# FTDI-Toolkit.net
KiCad netlist of a schematic drawn in Altium Designer
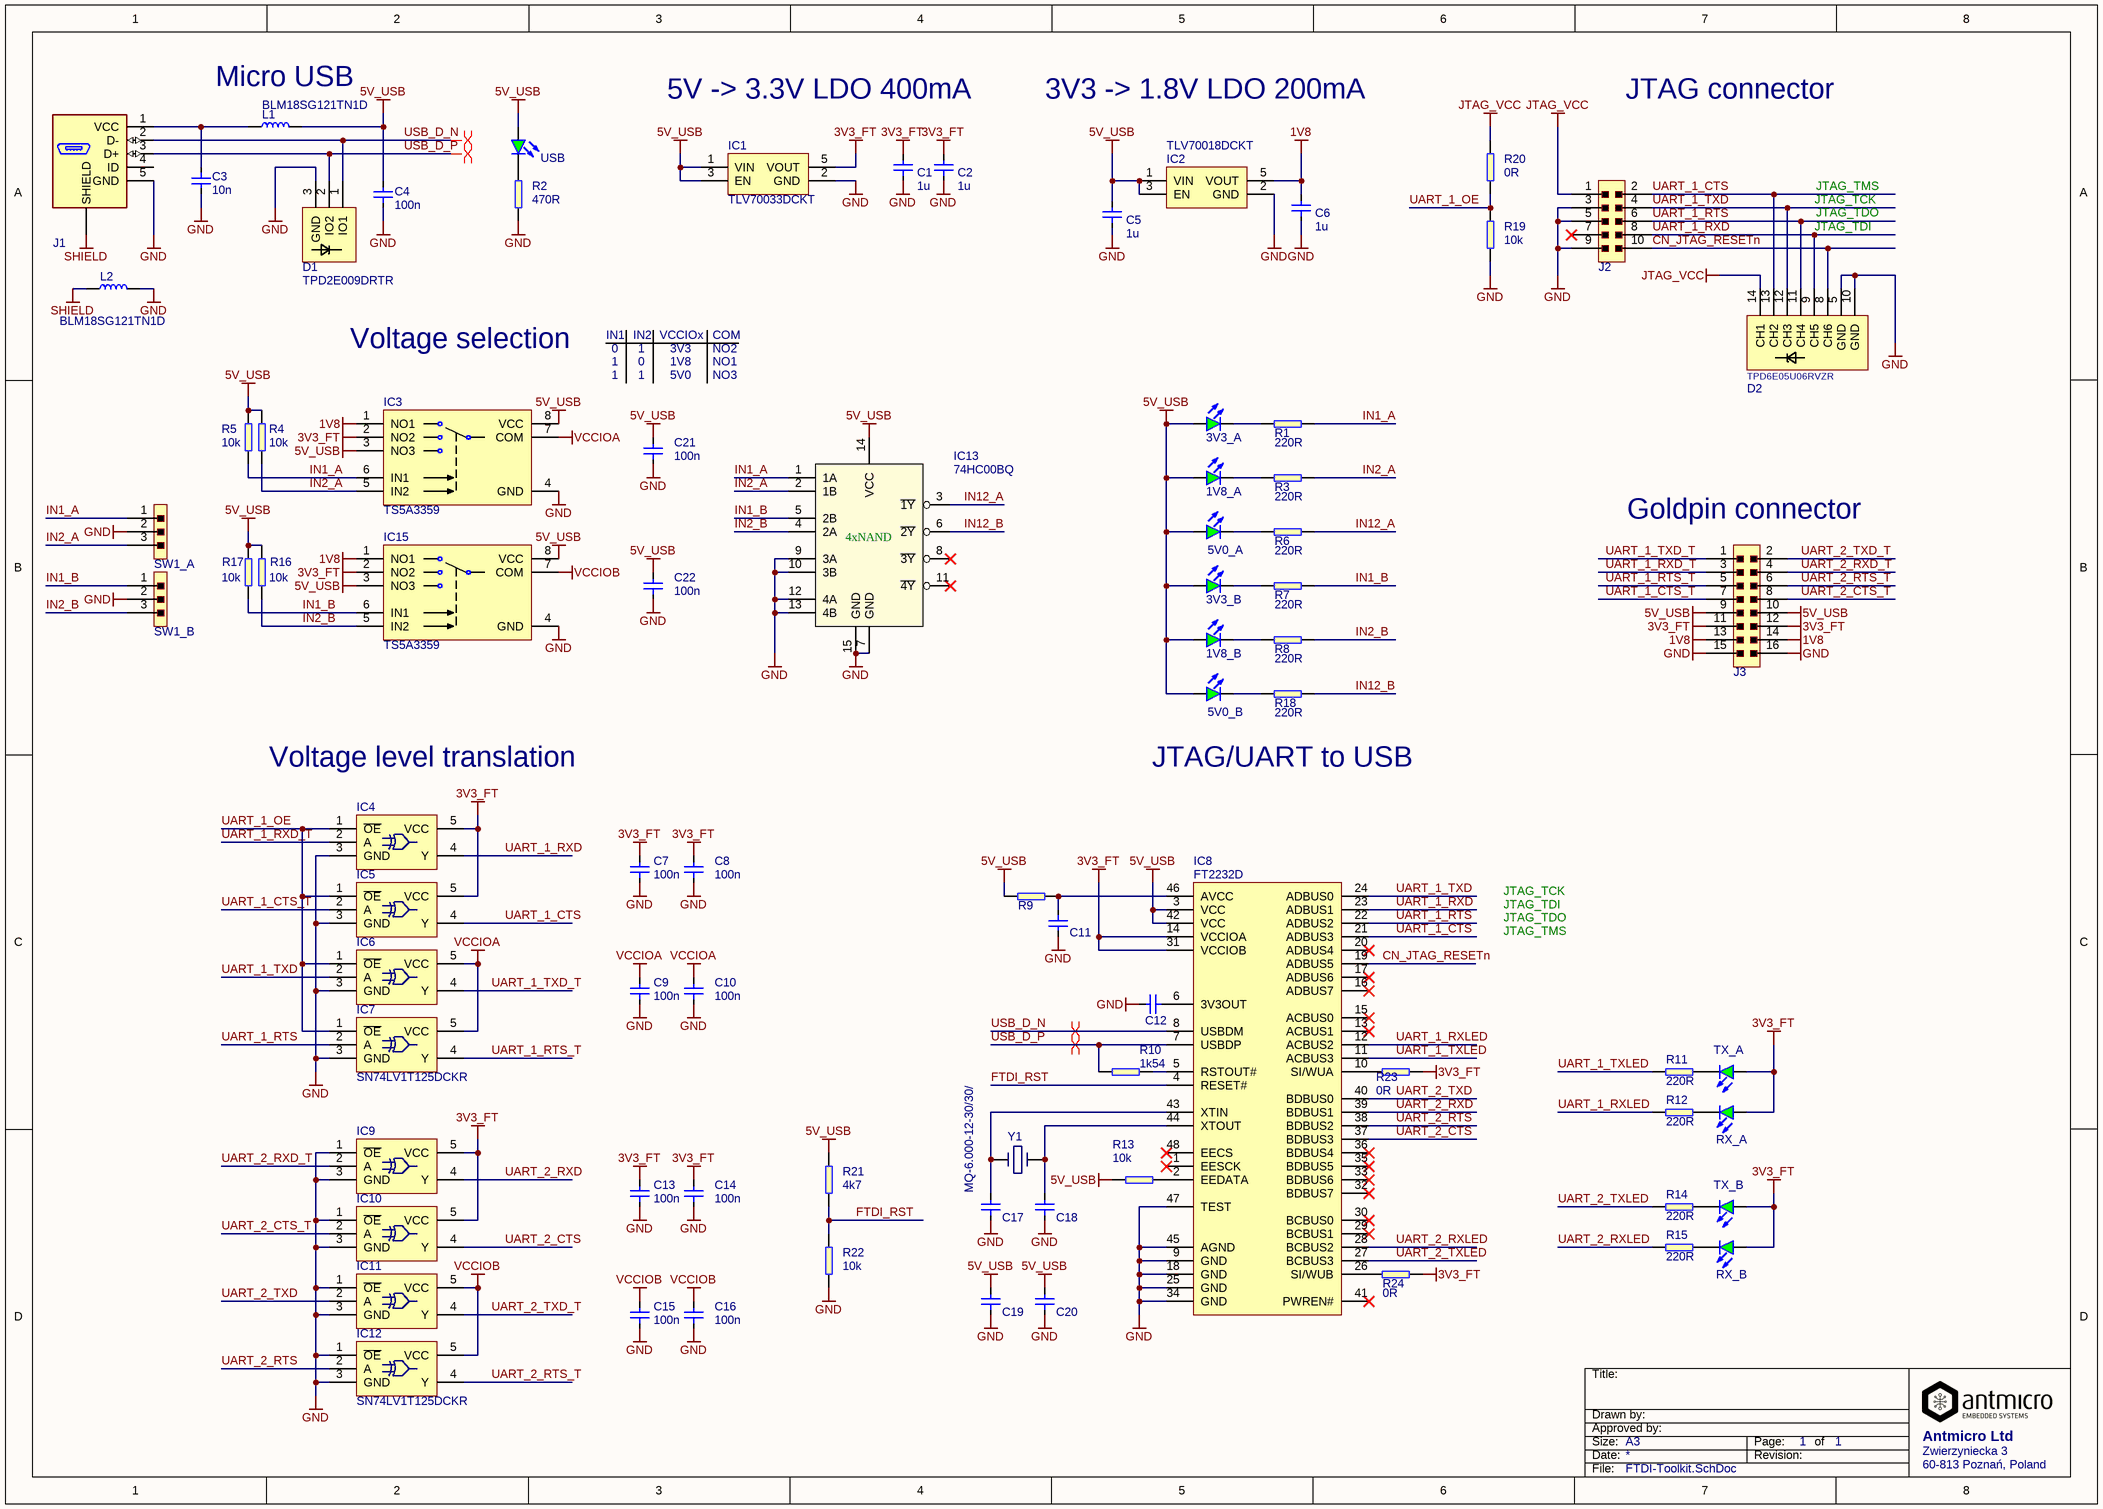
[diagram p0: FTDI-Toolkit.SchDoc]

(export (version "E")
  (design (tool "Eeschema 10.0.6"))
  (components
    (comp (ref "1V8_A")
      (value "KPT-1608SGC")
      (footprint "LED0603")
      (description "LED Green 0603 case")
      (fields (field (name "PARTNUMBER") "LED_G") (field (name "MANUFACTURER") "KINGBRIGHT"))
      (libsource (lib "AntmicroComponents") (part "LED"))
    )
    (comp (ref "1V8_B")
      (value "KPT-1608SGC")
      (footprint "LED0603")
      (description "LED Green 0603 case")
      (fields (field (name "PARTNUMBER") "LED_G") (field (name "MANUFACTURER") "KINGBRIGHT"))
      (libsource (lib "AntmicroComponents") (part "LED"))
    )
    (comp (ref "3V3_A")
      (value "KPT-1608SGC")
      (footprint "LED0603")
      (description "LED Green 0603 case")
      (fields (field (name "PARTNUMBER") "LED_G") (field (name "MANUFACTURER") "KINGBRIGHT"))
      (libsource (lib "AntmicroComponents") (part "LED"))
    )
    (comp (ref "3V3_B")
      (value "KPT-1608SGC")
      (footprint "LED0603")
      (description "LED Green 0603 case")
      (fields (field (name "PARTNUMBER") "LED_G") (field (name "MANUFACTURER") "KINGBRIGHT"))
      (libsource (lib "AntmicroComponents") (part "LED"))
    )
    (comp (ref "5V0_A")
      (value "KPT-1608SGC")
      (footprint "LED0603")
      (description "LED Green 0603 case")
      (fields (field (name "PARTNUMBER") "LED_G") (field (name "MANUFACTURER") "KINGBRIGHT"))
      (libsource (lib "AntmicroComponents") (part "LED"))
    )
    (comp (ref "5V0_B")
      (value "KPT-1608SGC")
      (footprint "LED0603")
      (description "LED Green 0603 case")
      (fields (field (name "PARTNUMBER") "LED_G") (field (name "MANUFACTURER") "KINGBRIGHT"))
      (libsource (lib "AntmicroComponents") (part "LED"))
    )
    (comp (ref "C1")
      (value "1u")
      (footprint "0603")
      (description "MLCC SMT Capacitor 1uF 0603")
      (fields (field (name "PARTNUMBER") "C_1u_0603") (field (name "MANUFACTURER") "Walsin"))
      (libsource (lib "AntmicroComponents") (part "C"))
    )
    (comp (ref "C2")
      (value "1u")
      (footprint "0603")
      (description "MLCC SMT Capacitor 1uF 0603")
      (fields (field (name "PARTNUMBER") "C_1u_0603") (field (name "MANUFACTURER") "Walsin"))
      (libsource (lib "AntmicroComponents") (part "C"))
    )
    (comp (ref "C3")
      (value "10n")
      (footprint "0402")
      (description "MLCC SMT Capacitor 10nF 0402")
      (fields (field (name "MANUFACTURER") "AVX") (field (name "MPN") "04025G103ZAT2A"))
      (libsource (lib "AntmicroComponents") (part "C"))
    )
    (comp (ref "C4")
      (value "100n")
      (footprint "0402")
      (description "MLCC SMT Capacitor 100nF 0402")
      (fields (field (name "MANUFACTURER") "Walsin") (field (name "MPN") "0402X104K6R3CT"))
      (libsource (lib "AntmicroComponents") (part "C"))
    )
    (comp (ref "C5")
      (value "1u")
      (footprint "0603")
      (description "MLCC SMT Capacitor 1uF 0603")
      (fields (field (name "PARTNUMBER") "C_1u_0603") (field (name "MANUFACTURER") "Walsin"))
      (libsource (lib "AntmicroComponents") (part "C"))
    )
    (comp (ref "C6")
      (value "1u")
      (footprint "0603")
      (description "MLCC SMT Capacitor 1uF 0603")
      (fields (field (name "PARTNUMBER") "C_1u_0603") (field (name "MANUFACTURER") "Walsin"))
      (libsource (lib "AntmicroComponents") (part "C"))
    )
    (comp (ref "C7")
      (value "100n")
      (footprint "0402")
      (description "MLCC SMT Capacitor 100nF 0402")
      (fields (field (name "PARTNUMBER") "C_100n_0402") (field (name "MANUFACTURER") "Walsin"))
      (libsource (lib "AntmicroComponents") (part "C"))
    )
    (comp (ref "C8")
      (value "100n")
      (footprint "0402")
      (description "MLCC SMT Capacitor 100nF 0402")
      (fields (field (name "PARTNUMBER") "C_100n_0402") (field (name "MANUFACTURER") "Walsin"))
      (libsource (lib "AntmicroComponents") (part "C"))
    )
    (comp (ref "C9")
      (value "100n")
      (footprint "0402")
      (description "MLCC SMT Capacitor 100nF 0402")
      (fields (field (name "PARTNUMBER") "C_100n_0402") (field (name "MANUFACTURER") "Walsin"))
      (libsource (lib "AntmicroComponents") (part "C"))
    )
    (comp (ref "C10")
      (value "100n")
      (footprint "0402")
      (description "MLCC SMT Capacitor 100nF 0402")
      (fields (field (name "PARTNUMBER") "C_100n_0402") (field (name "MANUFACTURER") "Walsin"))
      (libsource (lib "AntmicroComponents") (part "C"))
    )
    (comp (ref "C11")
      (value "100n")
      (footprint "0402")
      (description "MLCC SMT Capacitor 100nF 0402")
      (fields (field (name "PARTNUMBER") "C_100n_0402") (field (name "MANUFACTURER") "Walsin"))
      (libsource (lib "AntmicroComponents") (part "C"))
    )
    (comp (ref "C12")
      (value "100n")
      (footprint "0402")
      (description "MLCC SMT Capacitor 100nF 0402")
      (fields (field (name "PARTNUMBER") "C_100n_0402") (field (name "MANUFACTURER") "Walsin"))
      (libsource (lib "AntmicroComponents") (part "C"))
    )
    (comp (ref "C13")
      (value "100n")
      (footprint "0402")
      (description "MLCC SMT Capacitor 100nF 0402")
      (fields (field (name "PARTNUMBER") "C_100n_0402") (field (name "MANUFACTURER") "Walsin"))
      (libsource (lib "AntmicroComponents") (part "C"))
    )
    (comp (ref "C14")
      (value "100n")
      (footprint "0402")
      (description "MLCC SMT Capacitor 100nF 0402")
      (fields (field (name "PARTNUMBER") "C_100n_0402") (field (name "MANUFACTURER") "Walsin"))
      (libsource (lib "AntmicroComponents") (part "C"))
    )
    (comp (ref "C15")
      (value "100n")
      (footprint "0402")
      (description "MLCC SMT Capacitor 100nF 0402")
      (fields (field (name "PARTNUMBER") "C_100n_0402") (field (name "MANUFACTURER") "Walsin"))
      (libsource (lib "AntmicroComponents") (part "C"))
    )
    (comp (ref "C16")
      (value "100n")
      (footprint "0402")
      (description "MLCC SMT Capacitor 100nF 0402")
      (fields (field (name "PARTNUMBER") "C_100n_0402") (field (name "MANUFACTURER") "Walsin"))
      (libsource (lib "AntmicroComponents") (part "C"))
    )
    (comp (ref "C17")
      (value "27p")
      (footprint "0402")
      (description "MLCC SMT Capacitor 27pF 0402")
      (fields (field (name "PARTNUMBER") "C_27p_0402") (field (name "MANUFACTURER") "WALSIN"))
      (libsource (lib "AntmicroComponents") (part "C"))
    )
    (comp (ref "C18")
      (value "27p")
      (footprint "0402")
      (description "MLCC SMT Capacitor 27pF 0402")
      (fields (field (name "PARTNUMBER") "C_27p_0402") (field (name "MANUFACTURER") "WALSIN"))
      (libsource (lib "AntmicroComponents") (part "C"))
    )
    (comp (ref "C19")
      (value "100n")
      (footprint "0402")
      (description "MLCC SMT Capacitor 100nF 0402")
      (fields (field (name "PARTNUMBER") "C_100n_0402") (field (name "MANUFACTURER") "Walsin"))
      (libsource (lib "AntmicroComponents") (part "C"))
    )
    (comp (ref "C20")
      (value "100n")
      (footprint "0402")
      (description "MLCC SMT Capacitor 100nF 0402")
      (fields (field (name "PARTNUMBER") "C_100n_0402") (field (name "MANUFACTURER") "Walsin"))
      (libsource (lib "AntmicroComponents") (part "C"))
    )
    (comp (ref "C21")
      (value "100n")
      (footprint "0603")
      (description "MLCC SMT Capacitor 100nF 0603")
      (fields (field (name "PARTNUMBER") "C_100n_0603") (field (name "MANUFACTURER") "AVX"))
      (libsource (lib "AntmicroComponents") (part "C"))
    )
    (comp (ref "C22")
      (value "100n")
      (footprint "0603")
      (description "MLCC SMT Capacitor 100nF 0603")
      (fields (field (name "PARTNUMBER") "C_100n_0603") (field (name "MANUFACTURER") "AVX"))
      (libsource (lib "AntmicroComponents") (part "C"))
    )
    (comp (ref "D1")
      (value "TPD2E009DRTR")
      (footprint "SOT-3")
      (description "ESD Suppressors 2-CH")
      (fields (field (name "MANUFACTURER") "Texas Instruments"))
      (libsource (lib "AntmicroComponents") (part "TPD2E009"))
    )
    (comp (ref "D2")
      (value "TPD6E05U06")
      (footprint "TPD6E05U06_PASS")
      (description "ESD Suppressors 6-CH Pass through layout")
      (fields
        (field (name "PARTNUMBER") "TPD6E05U06_PASS")
        (field (name "MANUFACTURER") "Texas Instruments")
        (field (name "MPN") "TPD6E05U06RVZR")
      )
      (libsource (lib "AntmicroComponents") (part "TPD6E05U06"))
    )
    (comp (ref "IC1")
      (value "TLV70033DCKT")
      (footprint "SC70-5")
      (description "Voltage Regulator, 2V to 5.5V, 175mV Dropout, 3.3Vout, 200mAout")
      (fields (field (name "MANUFACTURER") "TEXAS INSTRUMENTS"))
      (libsource (lib "AntmicroComponents") (part "TLV700"))
    )
    (comp (ref "IC2")
      (value "TLV70018DCKT")
      (footprint "SC70-5")
      (description "Voltage Regulator, 2V to 5.5V, 175mV Dropout, 1.8Vout, 200mAout")
      (fields (field (name "MANUFACTURER") "TEXAS INSTRUMENTS"))
      (libsource (lib "AntmicroComponents") (part "TLV700"))
    )
    (comp (ref "IC3")
      (value "TS5A3359")
      (footprint "TS5A3359")
      (description "Analogue Switch, SP3T, 1 Channels, 0.9 ohm, 1.65V to 5.5V, VSSOP, 8 Pins")
      (fields (field (name "MANUFACTURER") "Texas Instruments"))
      (libsource (lib "AntmicroComponents") (part "TS5A3359"))
    )
    (comp (ref "IC4")
      (value "SN74LV1T125DCKR")
      (footprint "SC70-5")
      (description "Buffer, 74LV1T125, 1.6 V to 5.5 V, SOT-23-5")
      (fields (field (name "MANUFACTURER") "Texas Instruments"))
      (libsource (lib "AntmicroComponents") (part "SN74LV1T125"))
    )
    (comp (ref "IC5")
      (value "SN74LV1T125DCKR")
      (footprint "SC70-5")
      (description "Buffer, 74LV1T125, 1.6 V to 5.5 V, SOT-23-5")
      (fields (field (name "MANUFACTURER") "Texas Instruments"))
      (libsource (lib "AntmicroComponents") (part "SN74LV1T125"))
    )
    (comp (ref "IC6")
      (value "SN74LV1T125DCKR")
      (footprint "SC70-5")
      (description "Buffer, 74LV1T125, 1.6 V to 5.5 V, SOT-23-5")
      (fields (field (name "MANUFACTURER") "Texas Instruments"))
      (libsource (lib "AntmicroComponents") (part "SN74LV1T125"))
    )
    (comp (ref "IC7")
      (value "SN74LV1T125DCKR")
      (footprint "SC70-5")
      (description "Buffer, 74LV1T125, 1.6 V to 5.5 V, SOT-23-5")
      (fields (field (name "MANUFACTURER") "Texas Instruments"))
      (libsource (lib "AntmicroComponents") (part "SN74LV1T125"))
    )
    (comp (ref "IC8")
      (value "FT2232D")
      (footprint "LQFP-48")
      (description "Dual USB-UART/FIFO")
      (fields (field (name "MANUFACTURER") "FTDI") (field (name "MPN") "FT2232D-REEL"))
      (libsource (lib "AntmicroComponents") (part "FT2232"))
    )
    (comp (ref "IC9")
      (value "SN74LV1T125DCKR")
      (footprint "SC70-5")
      (description "Buffer, 74LV1T125, 1.6 V to 5.5 V, SOT-23-5")
      (fields (field (name "MANUFACTURER") "Texas Instruments"))
      (libsource (lib "AntmicroComponents") (part "SN74LV1T125"))
    )
    (comp (ref "IC10")
      (value "SN74LV1T125DCKR")
      (footprint "SC70-5")
      (description "Buffer, 74LV1T125, 1.6 V to 5.5 V, SOT-23-5")
      (fields (field (name "MANUFACTURER") "Texas Instruments"))
      (libsource (lib "AntmicroComponents") (part "SN74LV1T125"))
    )
    (comp (ref "IC11")
      (value "SN74LV1T125DCKR")
      (footprint "SC70-5")
      (description "Buffer, 74LV1T125, 1.6 V to 5.5 V, SOT-23-5")
      (fields (field (name "MANUFACTURER") "Texas Instruments"))
      (libsource (lib "AntmicroComponents") (part "SN74LV1T125"))
    )
    (comp (ref "IC12")
      (value "SN74LV1T125DCKR")
      (footprint "SC70-5")
      (description "Buffer, 74LV1T125, 1.6 V to 5.5 V, SOT-23-5")
      (fields (field (name "MANUFACTURER") "Texas Instruments"))
      (libsource (lib "AntmicroComponents") (part "SN74LV1T125"))
    )
    (comp (ref "IC13")
      (value "74HC00BQ")
      (footprint "DHVQFN14")
      (description "2 NAND Gate, 4 channel")
      (fields (field (name "MANUFACTURER") "NEXPERIA"))
      (libsource (lib "AntmicroComponents") (part "74HC00BQ"))
    )
    (comp (ref "IC15")
      (value "TS5A3359")
      (footprint "TS5A3359")
      (description "Analogue Switch, SP3T, 1 Channels, 0.9 ohm, 1.65V to 5.5V, VSSOP, 8 Pins")
      (fields (field (name "MANUFACTURER") "Texas Instruments"))
      (libsource (lib "AntmicroComponents") (part "TS5A3359"))
    )
    (comp (ref "J1")
      (value "629105150521")
      (footprint "WE_629105150521")
      (description "Micro USB B")
      (fields (field (name "MANUFACTURER") "WURTH ELEKTRONIK") (field (name "PARTNUMBER") "WE_629105150521"))
      (libsource (lib "AntmicroComponents") (part "Micro USB B"))
    )
    (comp (ref "J2")
      (value "SHF-105-01-L-D-SM")
      (footprint "SHF-105-01-X-D-SM")
      (description "10 Positions Header Connector 0.050\" (1.27mm) Surface Mount Gold")
      (fields (field (name "MANUFACTURER") "Samtec"))
      (libsource (lib "AntmicroComponents") (part "2X05"))
    )
    (comp (ref "J3")
      (value "MH_2X08_2.54_RA")
      (footprint "MH_2X08_2.54_RA")
      (description "Male header, 2 x 08 pins, pitch 2.54 mm, right angle")
      (fields (field (name "MANUFACTURER") "Amphenol") (field (name "MPN") "861400162LO1705LF"))
      (libsource (lib "AntmicroComponents") (part "2X08"))
    )
    (comp (ref "L1")
      (value "BLM18SG121TN1D")
      (footprint "0603")
      (description "FERRITE BEAD, 0.025OHM, 3A, 0603")
      (fields (field (name "MANUFACTURER") "MURATA"))
      (libsource (lib "AntmicroComponents") (part "Inductor SMT"))
    )
    (comp (ref "L2")
      (value "BLM18SG121TN1D")
      (footprint "0603")
      (description "FERRITE BEAD, 0.025OHM, 3A, 0603")
      (fields (field (name "MANUFACTURER") "MURATA"))
      (libsource (lib "AntmicroComponents") (part "Inductor SMT"))
    )
    (comp (ref "R1")
      (value "220R")
      (footprint "0402")
      (description "SMT Resistor 220R 0402")
      (fields
        (field (name "PARTNUMBER") "R_220R_0402")
        (field (name "MANUFACTURER") "TE CONNECTIVITY / NEOHM")
      )
      (libsource (lib "AntmicroComponents") (part "R"))
    )
    (comp (ref "R2")
      (value "470R")
      (footprint "0402")
      (description "SMT Resistor 470R 0402")
      (fields (field (name "MANUFACTURER") "VISHAY") (field (name "PARTNUMBER") "R_470R_0402"))
      (libsource (lib "") (part "R_1"))
    )
    (comp (ref "R3")
      (value "220R")
      (footprint "0402")
      (description "SMT Resistor 220R 0402")
      (fields
        (field (name "PARTNUMBER") "R_220R_0402")
        (field (name "MANUFACTURER") "TE CONNECTIVITY / NEOHM")
      )
      (libsource (lib "AntmicroComponents") (part "R"))
    )
    (comp (ref "R4")
      (value "10k")
      (footprint "0402")
      (description "SMT Resistor 0402")
      (fields (field (name "PARTNUMBER") "R_10k_0402") (field (name "TOLERANCE") "1%"))
      (libsource (lib "") (part "R_1"))
    )
    (comp (ref "R5")
      (value "10k")
      (footprint "0402")
      (description "SMT Resistor 0402")
      (fields (field (name "PARTNUMBER") "R_10k_0402") (field (name "TOLERANCE") "1%"))
      (libsource (lib "") (part "R_1"))
    )
    (comp (ref "R6")
      (value "220R")
      (footprint "0402")
      (description "SMT Resistor 220R 0402")
      (fields
        (field (name "PARTNUMBER") "R_220R_0402")
        (field (name "MANUFACTURER") "TE CONNECTIVITY / NEOHM")
      )
      (libsource (lib "AntmicroComponents") (part "R"))
    )
    (comp (ref "R7")
      (value "220R")
      (footprint "0402")
      (description "SMT Resistor 220R 0402")
      (fields
        (field (name "PARTNUMBER") "R_220R_0402")
        (field (name "MANUFACTURER") "TE CONNECTIVITY / NEOHM")
      )
      (libsource (lib "AntmicroComponents") (part "R"))
    )
    (comp (ref "R8")
      (value "220R")
      (footprint "0402")
      (description "SMT Resistor 220R 0402")
      (fields
        (field (name "PARTNUMBER") "R_220R_0402")
        (field (name "MANUFACTURER") "TE CONNECTIVITY / NEOHM")
      )
      (libsource (lib "AntmicroComponents") (part "R"))
    )
    (comp (ref "R9")
      (value "470R")
      (footprint "0402")
      (description "SMT Resistor 470R 0402")
      (fields (field (name "PARTNUMBER") "R_470R_0402") (field (name "MANUFACTURER") "VISHAY"))
      (libsource (lib "AntmicroComponents") (part "R"))
    )
    (comp (ref "R10")
      (value "1k54")
      (footprint "0402")
      (description "SMT Resistor 1k54 0402")
      (fields (field (name "PARTNUMBER") "R_1k54_0402") (field (name "TOLERANCE") "1%"))
      (libsource (lib "AntmicroComponents") (part "R"))
    )
    (comp (ref "R11")
      (value "220R")
      (footprint "0402")
      (description "SMT Resistor 220R 0402")
      (fields
        (field (name "PARTNUMBER") "R_220R_0402")
        (field (name "MANUFACTURER") "TE CONNECTIVITY / NEOHM")
      )
      (libsource (lib "AntmicroComponents") (part "R"))
    )
    (comp (ref "R12")
      (value "220R")
      (footprint "0402")
      (description "SMT Resistor 220R 0402")
      (fields
        (field (name "PARTNUMBER") "R_220R_0402")
        (field (name "MANUFACTURER") "TE CONNECTIVITY / NEOHM")
      )
      (libsource (lib "AntmicroComponents") (part "R"))
    )
    (comp (ref "R13")
      (value "10k")
      (footprint "0402")
      (description "SMT Resistor 0402")
      (fields (field (name "PARTNUMBER") "R_10k_0402") (field (name "TOLERANCE") "1%"))
      (libsource (lib "AntmicroComponents") (part "R"))
    )
    (comp (ref "R14")
      (value "220R")
      (footprint "0402")
      (description "SMT Resistor 220R 0402")
      (fields
        (field (name "PARTNUMBER") "R_220R_0402")
        (field (name "MANUFACTURER") "TE CONNECTIVITY / NEOHM")
      )
      (libsource (lib "AntmicroComponents") (part "R"))
    )
    (comp (ref "R15")
      (value "220R")
      (footprint "0402")
      (description "SMT Resistor 220R 0402")
      (fields
        (field (name "PARTNUMBER") "R_220R_0402")
        (field (name "MANUFACTURER") "TE CONNECTIVITY / NEOHM")
      )
      (libsource (lib "AntmicroComponents") (part "R"))
    )
    (comp (ref "R16")
      (value "10k")
      (footprint "0402")
      (description "SMT Resistor 0402")
      (fields (field (name "PARTNUMBER") "R_10k_0402") (field (name "TOLERANCE") "1%"))
      (libsource (lib "") (part "R_1"))
    )
    (comp (ref "R17")
      (value "10k")
      (footprint "0402")
      (description "SMT Resistor 0402")
      (fields (field (name "PARTNUMBER") "R_10k_0402") (field (name "TOLERANCE") "1%"))
      (libsource (lib "") (part "R_1"))
    )
    (comp (ref "R18")
      (value "220R")
      (footprint "0402")
      (description "SMT Resistor 220R 0402")
      (fields
        (field (name "PARTNUMBER") "R_220R_0402")
        (field (name "MANUFACTURER") "TE CONNECTIVITY / NEOHM")
      )
      (libsource (lib "AntmicroComponents") (part "R"))
    )
    (comp (ref "R19")
      (value "10k")
      (footprint "0402")
      (description "SMT Resistor 0402")
      (fields (field (name "PARTNUMBER") "R_10k_0402") (field (name "TOLERANCE") "1%"))
      (libsource (lib "") (part "R_1"))
    )
    (comp (ref "R20")
      (value "0R")
      (footprint "0402")
      (description "SMT Resistor 0402")
      (fields (field (name "PARTNUMBER") "R_0R_0402") (field (name "MANUFACTURER") "PANASONIC"))
      (libsource (lib "") (part "R_1"))
    )
    (comp (ref "R21")
      (value "4k7")
      (footprint "0402")
      (description "SMT Resistor 4k7 0402")
      (fields
        (field (name "PARTNUMBER") "R_4k7_0402")
        (field (name "MANUFACTURER") "PANASONIC ELECTRONIC COMPONENTS")
      )
      (libsource (lib "") (part "R_1"))
    )
    (comp (ref "R22")
      (value "10k")
      (footprint "0402")
      (description "SMT Resistor 0402")
      (fields (field (name "PARTNUMBER") "R_10k_0402") (field (name "TOLERANCE") "1%"))
      (libsource (lib "") (part "R_1"))
    )
    (comp (ref "R23")
      (value "0R")
      (footprint "0402")
      (description "SMT Resistor 0402")
      (fields (field (name "PARTNUMBER") "R_0R_0402") (field (name "MANUFACTURER") "PANASONIC"))
      (libsource (lib "AntmicroComponents") (part "R"))
    )
    (comp (ref "R24")
      (value "0R")
      (footprint "0402")
      (description "SMT Resistor 0402")
      (fields (field (name "PARTNUMBER") "R_0R_0402") (field (name "MANUFACTURER") "PANASONIC"))
      (libsource (lib "AntmicroComponents") (part "R"))
    )
    (comp (ref "RX_A")
      (value "KPT-1608SGC")
      (footprint "LED0603")
      (description "LED Green 0603 case")
      (fields (field (name "MANUFACTURER") "KINGBRIGHT") (field (name "PARTNUMBER") "LED_G"))
      (libsource (lib "AntmicroComponents") (part "LED"))
    )
    (comp (ref "RX_B")
      (value "KPT-1608SGC")
      (footprint "LED0603")
      (description "LED Green 0603 case")
      (fields (field (name "MANUFACTURER") "KINGBRIGHT") (field (name "PARTNUMBER") "LED_G"))
      (libsource (lib "AntmicroComponents") (part "LED"))
    )
    (comp (ref "SW1_A")
      (value "MH_1X03_2.54")
      (footprint "MH_1X03_2.54")
      (description "Male header, 1 x 03 pins, pitch 2.54 mm")
      (fields (field (name "MANUFACTURER") "HARWIN") (field (name "MPN") "M20-9990345."))
      (libsource (lib "AntmicroComponents") (part "1X03"))
    )
    (comp (ref "SW1_B")
      (value "MH_1X03_2.54")
      (footprint "MH_1X03_2.54")
      (description "Male header, 1 x 03 pins, pitch 2.54 mm")
      (fields (field (name "MANUFACTURER") "HARWIN") (field (name "MPN") "M20-9990345."))
      (libsource (lib "AntmicroComponents") (part "1X03"))
    )
    (comp (ref "TX_A")
      (value "KPT-1608SGC")
      (footprint "LED0603")
      (description "LED Green 0603 case")
      (fields (field (name "MANUFACTURER") "KINGBRIGHT") (field (name "PARTNUMBER") "LED_G"))
      (libsource (lib "AntmicroComponents") (part "LED"))
    )
    (comp (ref "TX_B")
      (value "KPT-1608SGC")
      (footprint "LED0603")
      (description "LED Green 0603 case")
      (fields (field (name "MANUFACTURER") "KINGBRIGHT") (field (name "PARTNUMBER") "LED_G"))
      (libsource (lib "AntmicroComponents") (part "LED"))
    )
    (comp (ref "USB")
      (value "KPT-1608SGC")
      (footprint "LED0603")
      (description "LED Green 0603 case")
      (fields (field (name "MANUFACTURER") "KINGBRIGHT") (field (name "PARTNUMBER") "LED_G"))
      (libsource (lib "AntmicroComponents") (part "LED"))
    )
    (comp (ref "Y1")
      (value "MQ-6.000-12-30/30/")
      (footprint "Crystal_5x7mm")
      (description "CRYSTAL, 6MHZ, 12PF, SMD,30ppm")
      (fields
        (field (name "PARTNUMBER") "CRYSTAL_6_MHz_SMD")
        (field (name "MANUFACTURER") "MERCURY UNITED ELECTRONICS")
      )
      (libsource (lib "AntmicroComponents") (part "CRYSTAL_6Mhz"))
    )
  )
  (nets
    (net (code "1") (name "/CN_JTAG_RESETn") (class "Default")
      (node (ref "D2") (pin "8") (pinfunction "CH6_8") (pintype "passive"))
      (node (ref "IC8") (pin "19") (pinfunction "ADBUS5_19") (pintype "passive"))
      (node (ref "J2") (pin "10") (pinfunction "10_10") (pintype "passive"))
    )
    (net (code "2") (name "/FTDI_RST") (class "Default")
      (node (ref "IC8") (pin "4") (pinfunction "RESET#_4") (pintype "passive"))
      (node (ref "R21") (pin "1") (pintype "passive"))
      (node (ref "R22") (pin "2") (pintype "passive"))
    )
    (net (code "3") (name "/IN1_A") (class "Default")
      (node (ref "IC13") (pin "1") (pinfunction "1A_1") (pintype "passive"))
      (node (ref "IC3") (pin "6") (pinfunction "IN1_6") (pintype "passive"))
      (node (ref "R1") (pin "2") (pintype "passive"))
      (node (ref "R5") (pin "1") (pintype "passive"))
      (node (ref "SW1_A") (pin "1") (pinfunction "1_1") (pintype "passive"))
    )
    (net (code "4") (name "/IN1_B") (class "Default")
      (node (ref "IC13") (pin "5") (pinfunction "2B_5") (pintype "passive"))
      (node (ref "IC15") (pin "6") (pinfunction "IN1_6") (pintype "passive"))
      (node (ref "R17") (pin "1") (pintype "passive"))
      (node (ref "R7") (pin "2") (pintype "passive"))
      (node (ref "SW1_B") (pin "1") (pinfunction "1_1") (pintype "passive"))
    )
    (net (code "5") (name "/IN2_A") (class "Default")
      (node (ref "IC13") (pin "2") (pinfunction "1B_2") (pintype "passive"))
      (node (ref "IC3") (pin "5") (pinfunction "IN2_5") (pintype "passive"))
      (node (ref "R3") (pin "2") (pintype "passive"))
      (node (ref "R4") (pin "1") (pintype "passive"))
      (node (ref "SW1_A") (pin "3") (pinfunction "3_3") (pintype "passive"))
    )
    (net (code "6") (name "/IN2_B") (class "Default")
      (node (ref "IC13") (pin "4") (pinfunction "2A_4") (pintype "passive"))
      (node (ref "IC15") (pin "5") (pinfunction "IN2_5") (pintype "passive"))
      (node (ref "R16") (pin "1") (pintype "passive"))
      (node (ref "R8") (pin "2") (pintype "passive"))
      (node (ref "SW1_B") (pin "3") (pinfunction "3_3") (pintype "passive"))
    )
    (net (code "7") (name "/IN12_A") (class "Default")
      (node (ref "IC13") (pin "3") (pinfunction "~{1Y}_3") (pintype "passive"))
      (node (ref "R6") (pin "2") (pintype "passive"))
    )
    (net (code "8") (name "/IN12_B") (class "Default")
      (node (ref "IC13") (pin "6") (pinfunction "~{2Y}_6") (pintype "passive"))
      (node (ref "R18") (pin "2") (pintype "passive"))
    )
    (net (code "9") (name "/UART_1_CTS") (class "Default")
      (node (ref "D2") (pin "13") (pinfunction "CH2_13") (pintype "passive"))
      (node (ref "IC5") (pin "4") (pinfunction "Y_4") (pintype "passive"))
      (node (ref "IC8") (pin "21") (pinfunction "ADBUS3_21") (pintype "passive"))
      (node (ref "J2") (pin "2") (pinfunction "2_2") (pintype "passive"))
    )
    (net (code "10") (name "/UART_1_CTS_T") (class "Default")
      (node (ref "IC5") (pin "2") (pinfunction "A_2") (pintype "passive"))
      (node (ref "J3") (pin "7") (pinfunction "7_7") (pintype "passive"))
    )
    (net (code "11") (name "/UART_1_OE") (class "Default")
      (node (ref "IC4") (pin "1") (pinfunction "~{OE}_1") (pintype "passive"))
      (node (ref "IC5") (pin "1") (pinfunction "~{OE}_1") (pintype "passive"))
      (node (ref "IC6") (pin "1") (pinfunction "~{OE}_1") (pintype "passive"))
      (node (ref "IC7") (pin "1") (pinfunction "~{OE}_1") (pintype "passive"))
      (node (ref "R19") (pin "2") (pintype "passive"))
      (node (ref "R20") (pin "1") (pintype "passive"))
    )
    (net (code "12") (name "/UART_1_RTS") (class "Default")
      (node (ref "D2") (pin "11") (pinfunction "CH4_11") (pintype "passive"))
      (node (ref "IC7") (pin "2") (pinfunction "A_2") (pintype "passive"))
      (node (ref "IC8") (pin "22") (pinfunction "ADBUS2_22") (pintype "passive"))
      (node (ref "J2") (pin "6") (pinfunction "6_6") (pintype "passive"))
    )
    (net (code "13") (name "/UART_1_RTS_T") (class "Default")
      (node (ref "IC7") (pin "4") (pinfunction "Y_4") (pintype "passive"))
      (node (ref "J3") (pin "5") (pinfunction "5_5") (pintype "passive"))
    )
    (net (code "14") (name "/UART_1_RXD") (class "Default")
      (node (ref "D2") (pin "9") (pinfunction "CH5_9") (pintype "passive"))
      (node (ref "IC4") (pin "4") (pinfunction "Y_4") (pintype "passive"))
      (node (ref "IC8") (pin "23") (pinfunction "ADBUS1_23") (pintype "passive"))
      (node (ref "J2") (pin "8") (pinfunction "8_8") (pintype "passive"))
    )
    (net (code "15") (name "/UART_1_RXD_T") (class "Default")
      (node (ref "IC4") (pin "2") (pinfunction "A_2") (pintype "passive"))
      (node (ref "J3") (pin "3") (pinfunction "3_3") (pintype "passive"))
    )
    (net (code "16") (name "/UART_1_RXLED") (class "Default")
      (node (ref "IC8") (pin "12") (pinfunction "ACBUS2_12") (pintype "passive"))
      (node (ref "R12") (pin "1") (pintype "passive"))
    )
    (net (code "17") (name "/UART_1_TXD") (class "Default")
      (node (ref "D2") (pin "12") (pinfunction "CH3_12") (pintype "passive"))
      (node (ref "IC6") (pin "2") (pinfunction "A_2") (pintype "passive"))
      (node (ref "IC8") (pin "24") (pinfunction "ADBUS0_24") (pintype "passive"))
      (node (ref "J2") (pin "4") (pinfunction "4_4") (pintype "passive"))
    )
    (net (code "18") (name "/UART_1_TXD_T") (class "Default")
      (node (ref "IC6") (pin "4") (pinfunction "Y_4") (pintype "passive"))
      (node (ref "J3") (pin "1") (pinfunction "1_1") (pintype "passive"))
    )
    (net (code "19") (name "/UART_1_TXLED") (class "Default")
      (node (ref "IC8") (pin "11") (pinfunction "ACBUS3_11") (pintype "passive"))
      (node (ref "R11") (pin "1") (pintype "passive"))
    )
    (net (code "20") (name "/UART_2_CTS") (class "Default")
      (node (ref "IC10") (pin "4") (pinfunction "Y_4") (pintype "passive"))
      (node (ref "IC8") (pin "37") (pinfunction "BDBUS3_37") (pintype "passive"))
    )
    (net (code "21") (name "/UART_2_CTS_T") (class "Default")
      (node (ref "IC10") (pin "2") (pinfunction "A_2") (pintype "passive"))
      (node (ref "J3") (pin "8") (pinfunction "8_8") (pintype "passive"))
    )
    (net (code "22") (name "/UART_2_RTS") (class "Default")
      (node (ref "IC12") (pin "2") (pinfunction "A_2") (pintype "passive"))
      (node (ref "IC8") (pin "38") (pinfunction "BDBUS2_38") (pintype "passive"))
    )
    (net (code "23") (name "/UART_2_RTS_T") (class "Default")
      (node (ref "IC12") (pin "4") (pinfunction "Y_4") (pintype "passive"))
      (node (ref "J3") (pin "6") (pinfunction "6_6") (pintype "passive"))
    )
    (net (code "24") (name "/UART_2_RXD") (class "Default")
      (node (ref "IC8") (pin "39") (pinfunction "BDBUS1_39") (pintype "passive"))
      (node (ref "IC9") (pin "4") (pinfunction "Y_4") (pintype "passive"))
    )
    (net (code "25") (name "/UART_2_RXD_T") (class "Default")
      (node (ref "IC9") (pin "2") (pinfunction "A_2") (pintype "passive"))
      (node (ref "J3") (pin "4") (pinfunction "4_4") (pintype "passive"))
    )
    (net (code "26") (name "/UART_2_RXLED") (class "Default")
      (node (ref "IC8") (pin "28") (pinfunction "BCBUS2_28") (pintype "passive"))
      (node (ref "R15") (pin "1") (pintype "passive"))
    )
    (net (code "27") (name "/UART_2_TXD") (class "Default")
      (node (ref "IC11") (pin "2") (pinfunction "A_2") (pintype "passive"))
      (node (ref "IC8") (pin "40") (pinfunction "BDBUS0_40") (pintype "passive"))
    )
    (net (code "28") (name "/UART_2_TXD_T") (class "Default")
      (node (ref "IC11") (pin "4") (pinfunction "Y_4") (pintype "passive"))
      (node (ref "J3") (pin "2") (pinfunction "2_2") (pintype "passive"))
    )
    (net (code "29") (name "/UART_2_TXLED") (class "Default")
      (node (ref "IC8") (pin "27") (pinfunction "BCBUS3_27") (pintype "passive"))
      (node (ref "R14") (pin "1") (pintype "passive"))
    )
    (net (code "30") (name "/USB_D_N") (class "Default")
      (node (ref "D1") (pin "1") (pinfunction "IO1_1") (pintype "passive"))
      (node (ref "IC8") (pin "8") (pinfunction "USBDM_8") (pintype "passive"))
      (node (ref "J1") (pin "2") (pinfunction "D-_2") (pintype "bidirectional"))
    )
    (net (code "31") (name "/USB_D_P") (class "Default")
      (node (ref "D1") (pin "2") (pinfunction "IO2_2") (pintype "passive"))
      (node (ref "IC8") (pin "7") (pinfunction "USBDP_7") (pintype "passive"))
      (node (ref "J1") (pin "3") (pinfunction "D+_3") (pintype "bidirectional"))
      (node (ref "R10") (pin "1") (pintype "passive"))
    )
    (net (code "32") (name "1V8") (class "Default")
      (node (ref "C6") (pin "2") (pinfunction "2_2") (pintype "passive"))
      (node (ref "IC15") (pin "1") (pinfunction "NO1_1") (pintype "passive"))
      (node (ref "IC2") (pin "5") (pinfunction "VOUT_5") (pintype "passive"))
      (node (ref "IC3") (pin "1") (pinfunction "NO1_1") (pintype "passive"))
      (node (ref "J3") (pin "13") (pinfunction "13_13") (pintype "passive"))
      (node (ref "J3") (pin "14") (pinfunction "14_14") (pintype "passive"))
    )
    (net (code "33") (name "3V3_FT") (class "Default")
      (node (ref "C1") (pin "2") (pinfunction "2_2") (pintype "passive"))
      (node (ref "C13") (pin "2") (pinfunction "2_2") (pintype "passive"))
      (node (ref "C14") (pin "2") (pinfunction "2_2") (pintype "passive"))
      (node (ref "C2") (pin "2") (pinfunction "2_2") (pintype "passive"))
      (node (ref "C7") (pin "2") (pinfunction "2_2") (pintype "passive"))
      (node (ref "C8") (pin "2") (pinfunction "2_2") (pintype "passive"))
      (node (ref "IC1") (pin "5") (pinfunction "VOUT_5") (pintype "passive"))
      (node (ref "IC10") (pin "5") (pinfunction "VCC_5") (pintype "passive"))
      (node (ref "IC15") (pin "2") (pinfunction "NO2_2") (pintype "passive"))
      (node (ref "IC3") (pin "2") (pinfunction "NO2_2") (pintype "passive"))
      (node (ref "IC4") (pin "5") (pinfunction "VCC_5") (pintype "passive"))
      (node (ref "IC5") (pin "5") (pinfunction "VCC_5") (pintype "passive"))
      (node (ref "IC8") (pin "14") (pinfunction "VCCIOA_14") (pintype "passive"))
      (node (ref "IC8") (pin "31") (pinfunction "VCCIOB_31") (pintype "passive"))
      (node (ref "IC9") (pin "5") (pinfunction "VCC_5") (pintype "passive"))
      (node (ref "J3") (pin "11") (pinfunction "11_11") (pintype "passive"))
      (node (ref "J3") (pin "12") (pinfunction "12_12") (pintype "passive"))
      (node (ref "R23") (pin "2") (pintype "passive"))
      (node (ref "R24") (pin "2") (pintype "passive"))
      (node (ref "RX_A") (pin "A") (pinfunction "A_A") (pintype "passive"))
      (node (ref "RX_B") (pin "A") (pinfunction "A_A") (pintype "passive"))
      (node (ref "TX_A") (pin "A") (pinfunction "A_A") (pintype "passive"))
      (node (ref "TX_B") (pin "A") (pinfunction "A_A") (pintype "passive"))
    )
    (net (code "34") (name "5V_USB") (class "Default")
      (node (ref "1V8_A") (pin "A") (pinfunction "A_A") (pintype "passive"))
      (node (ref "1V8_B") (pin "A") (pinfunction "A_A") (pintype "passive"))
      (node (ref "3V3_A") (pin "A") (pinfunction "A_A") (pintype "passive"))
      (node (ref "3V3_B") (pin "A") (pinfunction "A_A") (pintype "passive"))
      (node (ref "5V0_A") (pin "A") (pinfunction "A_A") (pintype "passive"))
      (node (ref "5V0_B") (pin "A") (pinfunction "A_A") (pintype "passive"))
      (node (ref "C19") (pin "2") (pinfunction "2_2") (pintype "passive"))
      (node (ref "C20") (pin "2") (pinfunction "2_2") (pintype "passive"))
      (node (ref "C21") (pin "2") (pinfunction "2_2") (pintype "passive"))
      (node (ref "C22") (pin "2") (pinfunction "2_2") (pintype "passive"))
      (node (ref "C4") (pin "2") (pinfunction "2_2") (pintype "passive"))
      (node (ref "C5") (pin "2") (pinfunction "2_2") (pintype "passive"))
      (node (ref "IC1") (pin "1") (pinfunction "VIN_1") (pintype "passive"))
      (node (ref "IC1") (pin "3") (pinfunction "EN_3") (pintype "passive"))
      (node (ref "IC13") (pin "14") (pinfunction "VCC_14") (pintype "passive"))
      (node (ref "IC15") (pin "3") (pinfunction "NO3_3") (pintype "passive"))
      (node (ref "IC15") (pin "8") (pinfunction "VCC_8") (pintype "passive"))
      (node (ref "IC2") (pin "1") (pinfunction "VIN_1") (pintype "passive"))
      (node (ref "IC2") (pin "3") (pinfunction "EN_3") (pintype "passive"))
      (node (ref "IC3") (pin "3") (pinfunction "NO3_3") (pintype "passive"))
      (node (ref "IC3") (pin "8") (pinfunction "VCC_8") (pintype "passive"))
      (node (ref "IC8") (pin "3") (pinfunction "VCC_3") (pintype "passive"))
      (node (ref "IC8") (pin "42") (pinfunction "VCC_42") (pintype "passive"))
      (node (ref "J3") (pin "10") (pinfunction "10_10") (pintype "passive"))
      (node (ref "J3") (pin "9") (pinfunction "9_9") (pintype "passive"))
      (node (ref "L1") (pin "1") (pintype "passive"))
      (node (ref "R13") (pin "1") (pintype "passive"))
      (node (ref "R16") (pin "2") (pintype "passive"))
      (node (ref "R17") (pin "2") (pintype "passive"))
      (node (ref "R21") (pin "2") (pintype "passive"))
      (node (ref "R4") (pin "2") (pintype "passive"))
      (node (ref "R5") (pin "2") (pintype "passive"))
      (node (ref "R9") (pin "1") (pintype "passive"))
      (node (ref "USB") (pin "A") (pinfunction "A_A") (pintype "passive"))
    )
    (net (code "35") (name "GND") (class "Default")
      (node (ref "C1") (pin "1") (pinfunction "1_1") (pintype "passive"))
      (node (ref "C10") (pin "1") (pinfunction "1_1") (pintype "passive"))
      (node (ref "C11") (pin "2") (pinfunction "2_2") (pintype "passive"))
      (node (ref "C12") (pin "2") (pinfunction "2_2") (pintype "passive"))
      (node (ref "C13") (pin "1") (pinfunction "1_1") (pintype "passive"))
      (node (ref "C14") (pin "1") (pinfunction "1_1") (pintype "passive"))
      (node (ref "C15") (pin "1") (pinfunction "1_1") (pintype "passive"))
      (node (ref "C16") (pin "1") (pinfunction "1_1") (pintype "passive"))
      (node (ref "C17") (pin "1") (pinfunction "1_1") (pintype "passive"))
      (node (ref "C18") (pin "1") (pinfunction "1_1") (pintype "passive"))
      (node (ref "C19") (pin "1") (pinfunction "1_1") (pintype "passive"))
      (node (ref "C2") (pin "1") (pinfunction "1_1") (pintype "passive"))
      (node (ref "C20") (pin "1") (pinfunction "1_1") (pintype "passive"))
      (node (ref "C21") (pin "1") (pinfunction "1_1") (pintype "passive"))
      (node (ref "C22") (pin "1") (pinfunction "1_1") (pintype "passive"))
      (node (ref "C3") (pin "2") (pinfunction "2_2") (pintype "passive"))
      (node (ref "C4") (pin "1") (pinfunction "1_1") (pintype "passive"))
      (node (ref "C5") (pin "1") (pinfunction "1_1") (pintype "passive"))
      (node (ref "C6") (pin "1") (pinfunction "1_1") (pintype "passive"))
      (node (ref "C7") (pin "1") (pinfunction "1_1") (pintype "passive"))
      (node (ref "C8") (pin "1") (pinfunction "1_1") (pintype "passive"))
      (node (ref "C9") (pin "1") (pinfunction "1_1") (pintype "passive"))
      (node (ref "D1") (pin "3") (pinfunction "GND_3") (pintype "passive"))
      (node (ref "D2") (pin "10") (pinfunction "GND_10") (pintype "passive"))
      (node (ref "D2") (pin "5") (pinfunction "GND_5") (pintype "passive"))
      (node (ref "IC1") (pin "2") (pinfunction "GND_2") (pintype "passive"))
      (node (ref "IC10") (pin "1") (pinfunction "~{OE}_1") (pintype "passive"))
      (node (ref "IC10") (pin "3") (pinfunction "GND_3") (pintype "passive"))
      (node (ref "IC11") (pin "1") (pinfunction "~{OE}_1") (pintype "passive"))
      (node (ref "IC11") (pin "3") (pinfunction "GND_3") (pintype "passive"))
      (node (ref "IC12") (pin "1") (pinfunction "~{OE}_1") (pintype "passive"))
      (node (ref "IC12") (pin "3") (pinfunction "GND_3") (pintype "passive"))
      (node (ref "IC13") (pin "10") (pinfunction "3B_10") (pintype "passive"))
      (node (ref "IC13") (pin "12") (pinfunction "4A_12") (pintype "passive"))
      (node (ref "IC13") (pin "13") (pinfunction "4B_13") (pintype "passive"))
      (node (ref "IC13") (pin "15") (pinfunction "GND_15") (pintype "passive"))
      (node (ref "IC13") (pin "7") (pinfunction "GND_7") (pintype "passive"))
      (node (ref "IC13") (pin "9") (pinfunction "3A_9") (pintype "passive"))
      (node (ref "IC15") (pin "4") (pinfunction "GND_4") (pintype "passive"))
      (node (ref "IC2") (pin "2") (pinfunction "GND_2") (pintype "passive"))
      (node (ref "IC3") (pin "4") (pinfunction "GND_4") (pintype "passive"))
      (node (ref "IC4") (pin "3") (pinfunction "GND_3") (pintype "passive"))
      (node (ref "IC5") (pin "3") (pinfunction "GND_3") (pintype "passive"))
      (node (ref "IC6") (pin "3") (pinfunction "GND_3") (pintype "passive"))
      (node (ref "IC7") (pin "3") (pinfunction "GND_3") (pintype "passive"))
      (node (ref "IC8") (pin "18") (pinfunction "GND_18") (pintype "passive"))
      (node (ref "IC8") (pin "25") (pinfunction "GND_25") (pintype "passive"))
      (node (ref "IC8") (pin "34") (pinfunction "GND_34") (pintype "passive"))
      (node (ref "IC8") (pin "45") (pinfunction "AGND_45") (pintype "passive"))
      (node (ref "IC8") (pin "47") (pinfunction "TEST_47") (pintype "passive"))
      (node (ref "IC8") (pin "9") (pinfunction "GND_9") (pintype "passive"))
      (node (ref "IC9") (pin "1") (pinfunction "~{OE}_1") (pintype "passive"))
      (node (ref "IC9") (pin "3") (pinfunction "GND_3") (pintype "passive"))
      (node (ref "J1") (pin "5") (pinfunction "GND_5") (pintype "power_in"))
      (node (ref "J2") (pin "3") (pinfunction "3_3") (pintype "passive"))
      (node (ref "J2") (pin "5") (pinfunction "5_5") (pintype "passive"))
      (node (ref "J2") (pin "9") (pinfunction "9_9") (pintype "passive"))
      (node (ref "J3") (pin "15") (pinfunction "15_15") (pintype "passive"))
      (node (ref "J3") (pin "16") (pinfunction "16_16") (pintype "passive"))
      (node (ref "L2") (pin "1") (pintype "passive"))
      (node (ref "R19") (pin "1") (pintype "passive"))
      (node (ref "R2") (pin "1") (pintype "passive"))
      (node (ref "R22") (pin "1") (pintype "passive"))
      (node (ref "SW1_A") (pin "2") (pinfunction "2_2") (pintype "passive"))
      (node (ref "SW1_B") (pin "2") (pinfunction "2_2") (pintype "passive"))
    )
    (net (code "36") (name "JTAG_VCC") (class "Default")
      (node (ref "D2") (pin "14") (pinfunction "CH1_14") (pintype "passive"))
      (node (ref "J2") (pin "1") (pinfunction "1_1") (pintype "passive"))
      (node (ref "R20") (pin "2") (pintype "passive"))
    )
    (net (code "37") (name "Net-(1V8_A-PadK)") (class "Default")
      (node (ref "1V8_A") (pin "K") (pinfunction "K_K") (pintype "passive"))
      (node (ref "R3") (pin "1") (pintype "passive"))
    )
    (net (code "38") (name "Net-(1V8_B-PadK)") (class "Default")
      (node (ref "1V8_B") (pin "K") (pinfunction "K_K") (pintype "passive"))
      (node (ref "R8") (pin "1") (pintype "passive"))
    )
    (net (code "39") (name "Net-(3V3_A-PadK)") (class "Default")
      (node (ref "3V3_A") (pin "K") (pinfunction "K_K") (pintype "passive"))
      (node (ref "R1") (pin "1") (pintype "passive"))
    )
    (net (code "40") (name "Net-(3V3_B-PadK)") (class "Default")
      (node (ref "3V3_B") (pin "K") (pinfunction "K_K") (pintype "passive"))
      (node (ref "R7") (pin "1") (pintype "passive"))
    )
    (net (code "41") (name "Net-(5V0_A-PadK)") (class "Default")
      (node (ref "5V0_A") (pin "K") (pinfunction "K_K") (pintype "passive"))
      (node (ref "R6") (pin "1") (pintype "passive"))
    )
    (net (code "42") (name "Net-(5V0_B-PadK)") (class "Default")
      (node (ref "5V0_B") (pin "K") (pinfunction "K_K") (pintype "passive"))
      (node (ref "R18") (pin "1") (pintype "passive"))
    )
    (net (code "43") (name "Net-(IC8-3V3OUT)") (class "Default")
      (node (ref "C12") (pin "1") (pinfunction "1_1") (pintype "passive"))
      (node (ref "IC8") (pin "6") (pinfunction "3V3OUT_6") (pintype "passive"))
    )
    (net (code "44") (name "Net-(IC8-AVCC)") (class "Default")
      (node (ref "C11") (pin "1") (pinfunction "1_1") (pintype "passive"))
      (node (ref "IC8") (pin "46") (pinfunction "AVCC_46") (pintype "passive"))
      (node (ref "R9") (pin "2") (pintype "passive"))
    )
    (net (code "45") (name "Net-(IC8-EEDATA)") (class "Default")
      (node (ref "IC8") (pin "2") (pinfunction "EEDATA_2") (pintype "passive"))
      (node (ref "R13") (pin "2") (pintype "passive"))
    )
    (net (code "46") (name "Net-(IC8-RSTOUT#)") (class "Default")
      (node (ref "IC8") (pin "5") (pinfunction "RSTOUT#_5") (pintype "passive"))
      (node (ref "R10") (pin "2") (pintype "passive"))
    )
    (net (code "47") (name "Net-(IC8-SI{slash}WUA)") (class "Default")
      (node (ref "IC8") (pin "10") (pinfunction "SI/WUA_10") (pintype "passive"))
      (node (ref "R23") (pin "1") (pintype "passive"))
    )
    (net (code "48") (name "Net-(IC8-SI{slash}WUB)") (class "Default")
      (node (ref "IC8") (pin "26") (pinfunction "SI/WUB_26") (pintype "passive"))
      (node (ref "R24") (pin "1") (pintype "passive"))
    )
    (net (code "49") (name "Net-(IC8-XTIN)") (class "Default")
      (node (ref "C17") (pin "2") (pinfunction "2_2") (pintype "passive"))
      (node (ref "IC8") (pin "43") (pinfunction "XTIN_43") (pintype "passive"))
      (node (ref "Y1") (pin "1") (pinfunction "1_1") (pintype "passive"))
    )
    (net (code "50") (name "Net-(IC8-XTOUT)") (class "Default")
      (node (ref "C18") (pin "2") (pinfunction "2_2") (pintype "passive"))
      (node (ref "IC8") (pin "44") (pinfunction "XTOUT_44") (pintype "passive"))
      (node (ref "Y1") (pin "3") (pinfunction "3_3") (pintype "passive"))
    )
    (net (code "51") (name "Net-(J1-VCC)") (class "Default")
      (node (ref "C3") (pin "1") (pinfunction "1_1") (pintype "passive"))
      (node (ref "J1") (pin "1") (pinfunction "VCC_1") (pintype "power_in"))
      (node (ref "L1") (pin "2") (pintype "passive"))
    )
    (net (code "52") (name "Net-(R2-Pad2)") (class "Default")
      (node (ref "R2") (pin "2") (pintype "passive"))
      (node (ref "USB") (pin "K") (pinfunction "K_K") (pintype "passive"))
    )
    (net (code "53") (name "Net-(R11-Pad2)") (class "Default")
      (node (ref "R11") (pin "2") (pintype "passive"))
      (node (ref "TX_A") (pin "K") (pinfunction "K_K") (pintype "passive"))
    )
    (net (code "54") (name "Net-(R12-Pad2)") (class "Default")
      (node (ref "R12") (pin "2") (pintype "passive"))
      (node (ref "RX_A") (pin "K") (pinfunction "K_K") (pintype "passive"))
    )
    (net (code "55") (name "Net-(R14-Pad2)") (class "Default")
      (node (ref "R14") (pin "2") (pintype "passive"))
      (node (ref "TX_B") (pin "K") (pinfunction "K_K") (pintype "passive"))
    )
    (net (code "56") (name "Net-(R15-Pad2)") (class "Default")
      (node (ref "R15") (pin "2") (pintype "passive"))
      (node (ref "RX_B") (pin "K") (pinfunction "K_K") (pintype "passive"))
    )
    (net (code "57") (name "SHIELD") (class "Default")
      (node (ref "J1") (pin "S") (pinfunction "SHIELD_S") (pintype "passive"))
      (node (ref "L2") (pin "2") (pintype "passive"))
    )
    (net (code "58") (name "VCCIOA") (class "Default")
      (node (ref "C10") (pin "2") (pinfunction "2_2") (pintype "passive"))
      (node (ref "C9") (pin "2") (pinfunction "2_2") (pintype "passive"))
      (node (ref "IC3") (pin "7") (pinfunction "COM_7") (pintype "passive"))
      (node (ref "IC6") (pin "5") (pinfunction "VCC_5") (pintype "passive"))
      (node (ref "IC7") (pin "5") (pinfunction "VCC_5") (pintype "passive"))
    )
    (net (code "59") (name "VCCIOB") (class "Default")
      (node (ref "C15") (pin "2") (pinfunction "2_2") (pintype "passive"))
      (node (ref "C16") (pin "2") (pinfunction "2_2") (pintype "passive"))
      (node (ref "IC11") (pin "5") (pinfunction "VCC_5") (pintype "passive"))
      (node (ref "IC12") (pin "5") (pinfunction "VCC_5") (pintype "passive"))
      (node (ref "IC15") (pin "7") (pinfunction "COM_7") (pintype "passive"))
    )
    (net (code "60") (name "unconnected-(IC8-ACBUS0-Pad15)") (class "Default")
      (node (ref "IC8") (pin "15") (pinfunction "ACBUS0_15") (pintype "passive+no_connect"))
    )
    (net (code "61") (name "unconnected-(IC8-ACBUS1-Pad13)") (class "Default")
      (node (ref "IC8") (pin "13") (pinfunction "ACBUS1_13") (pintype "passive+no_connect"))
    )
    (net (code "62") (name "unconnected-(IC8-ADBUS4-Pad20)") (class "Default")
      (node (ref "IC8") (pin "20") (pinfunction "ADBUS4_20") (pintype "passive+no_connect"))
    )
    (net (code "63") (name "unconnected-(IC8-ADBUS6-Pad17)") (class "Default")
      (node (ref "IC8") (pin "17") (pinfunction "ADBUS6_17") (pintype "passive+no_connect"))
    )
    (net (code "64") (name "unconnected-(IC8-ADBUS7-Pad16)") (class "Default")
      (node (ref "IC8") (pin "16") (pinfunction "ADBUS7_16") (pintype "passive+no_connect"))
    )
    (net (code "65") (name "unconnected-(IC8-BCBUS0-Pad30)") (class "Default")
      (node (ref "IC8") (pin "30") (pinfunction "BCBUS0_30") (pintype "passive+no_connect"))
    )
    (net (code "66") (name "unconnected-(IC8-BCBUS1-Pad29)") (class "Default")
      (node (ref "IC8") (pin "29") (pinfunction "BCBUS1_29") (pintype "passive+no_connect"))
    )
    (net (code "67") (name "unconnected-(IC8-BDBUS4-Pad36)") (class "Default")
      (node (ref "IC8") (pin "36") (pinfunction "BDBUS4_36") (pintype "passive+no_connect"))
    )
    (net (code "68") (name "unconnected-(IC8-BDBUS5-Pad35)") (class "Default")
      (node (ref "IC8") (pin "35") (pinfunction "BDBUS5_35") (pintype "passive+no_connect"))
    )
    (net (code "69") (name "unconnected-(IC8-BDBUS6-Pad33)") (class "Default")
      (node (ref "IC8") (pin "33") (pinfunction "BDBUS6_33") (pintype "passive+no_connect"))
    )
    (net (code "70") (name "unconnected-(IC8-BDBUS7-Pad32)") (class "Default")
      (node (ref "IC8") (pin "32") (pinfunction "BDBUS7_32") (pintype "passive+no_connect"))
    )
    (net (code "71") (name "unconnected-(IC8-EECS-Pad48)") (class "Default")
      (node (ref "IC8") (pin "48") (pinfunction "EECS_48") (pintype "passive+no_connect"))
    )
    (net (code "72") (name "unconnected-(IC8-EESCK-Pad1)") (class "Default")
      (node (ref "IC8") (pin "1") (pinfunction "EESCK_1") (pintype "passive+no_connect"))
    )
    (net (code "73") (name "unconnected-(IC8-PWREN#-Pad41)") (class "Default")
      (node (ref "IC8") (pin "41") (pinfunction "PWREN#_41") (pintype "passive+no_connect"))
    )
    (net (code "74") (name "unconnected-(IC13-~{3Y}-Pad8)") (class "Default")
      (node (ref "IC13") (pin "8") (pinfunction "~{3Y}_8") (pintype "passive+no_connect"))
    )
    (net (code "75") (name "unconnected-(IC13-~{4Y}-Pad11)") (class "Default")
      (node (ref "IC13") (pin "11") (pinfunction "~{4Y}_11") (pintype "passive+no_connect"))
    )
    (net (code "76") (name "unconnected-(J1-ID-Pad4)") (class "Default")
      (node (ref "J1") (pin "4") (pinfunction "ID_4") (pintype "passive"))
    )
    (net (code "77") (name "unconnected-(J2-Pad7)") (class "Default")
      (node (ref "J2") (pin "7") (pinfunction "7_7") (pintype "passive+no_connect"))
    )
  )
)
